# Versorgungseinheit_v1.net
KiCad netlist of a schematic drawn in EAGLE
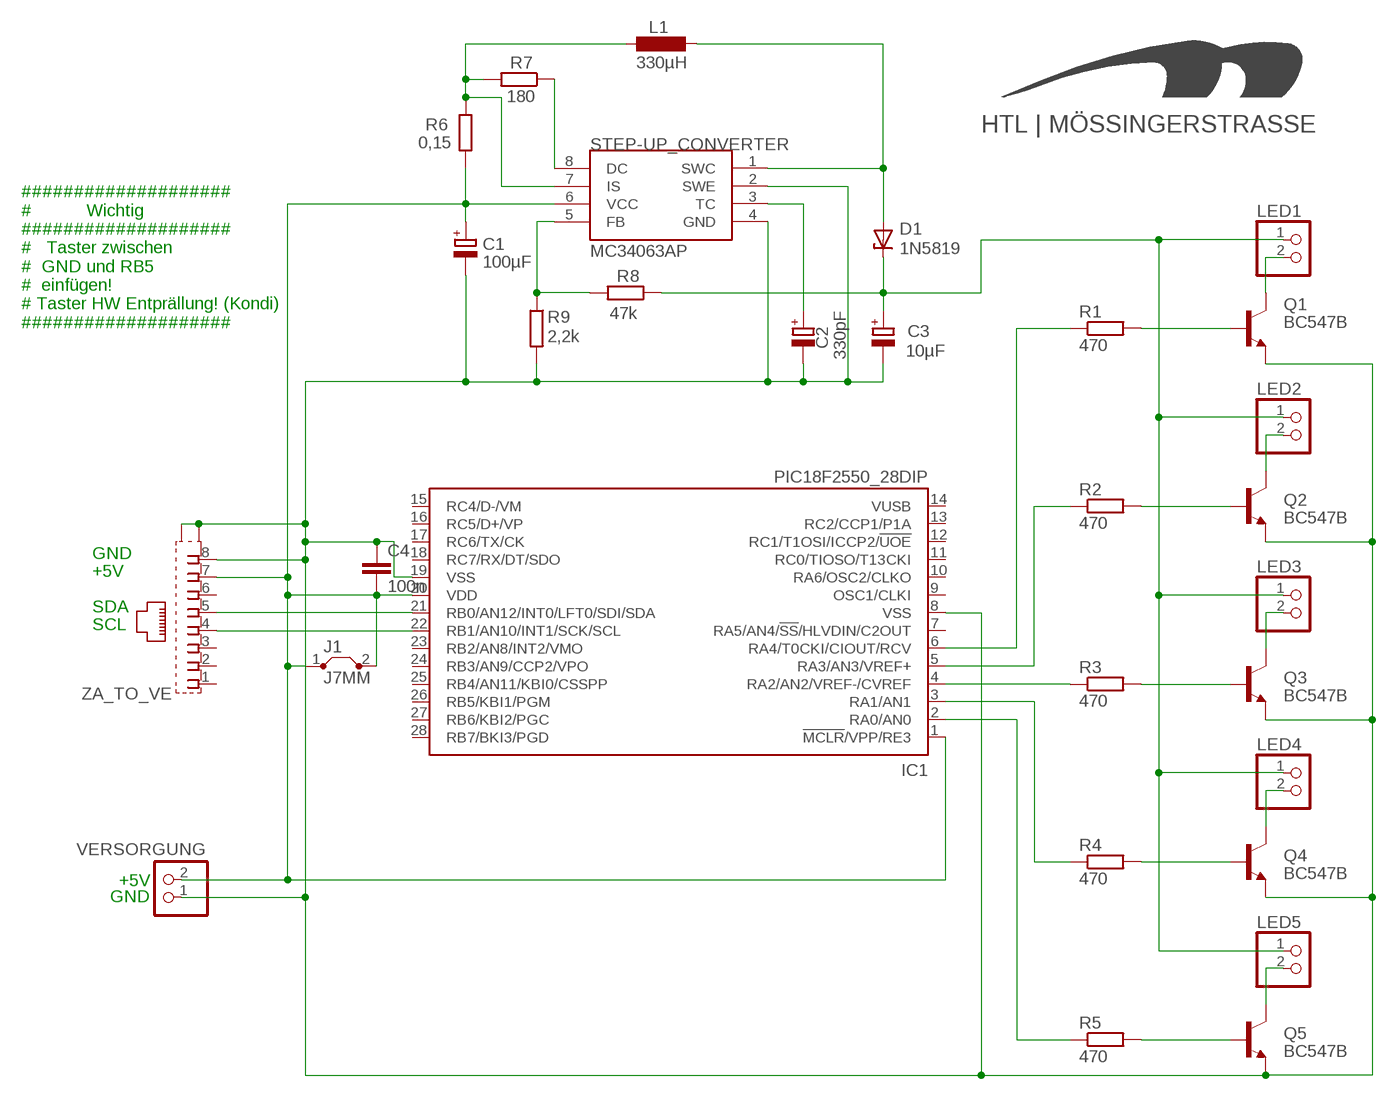
[diagram p0: schematic, sheet 1]

(export (version "E")
  (design (tool "Eeschema 10.0.6"))
  (components
    (comp (ref "C1")
      (value "100µF")
      (footprint "eagle-import:E5-8,5")
      (libsource (lib "eagle-import") (part "CPOL-EUE5-8.5"))
    )
    (comp (ref "C2")
      (value "330pF")
      (footprint "eagle-import:E5-8,5")
      (libsource (lib "eagle-import") (part "CPOL-EUE5-8.5"))
    )
    (comp (ref "C3")
      (value "10µF")
      (footprint "eagle-import:E5-8,5")
      (libsource (lib "eagle-import") (part "CPOL-EUE5-8.5"))
    )
    (comp (ref "C4")
      (value "100n")
      (footprint "eagle-import:C050-025X075")
      (libsource (lib "eagle-import") (part "C-EU050-025X075"))
    )
    (comp (ref "D1")
      (value "1N5819")
      (footprint "eagle-import:DO41Z10")
      (libsource (lib "eagle-import") (part "1N4728"))
    )
    (comp (ref "IC1")
      (value "PIC18F2550_28DIP")
      (footprint "eagle-import:DIL28-3")
      (fields (field (name "MF") "MICROCHIP") (field (name "MPN") "PIC18F2550-I/SP"))
      (libsource (lib "eagle-import") (part "PIC18F2_28DIP550"))
    )
    (comp (ref "J1")
      (value "J7MM")
      (footprint "eagle-import:07")
      (libsource (lib "eagle-import") (part "J7MM"))
    )
    (comp (ref "L1")
      (value "330µH")
      (footprint "eagle-import:0207_10")
      (libsource (lib "eagle-import") (part "L-EU0207/10"))
    )
    (comp (ref "LED1")
      (value "PINHD-1X2")
      (footprint "eagle-import:1X02")
      (libsource (lib "eagle-import") (part "PINHD-1X2"))
    )
    (comp (ref "LED2")
      (value "PINHD-1X2")
      (footprint "eagle-import:1X02")
      (libsource (lib "eagle-import") (part "PINHD-1X2"))
    )
    (comp (ref "LED3")
      (value "PINHD-1X2")
      (footprint "eagle-import:1X02")
      (libsource (lib "eagle-import") (part "PINHD-1X2"))
    )
    (comp (ref "LED4")
      (value "PINHD-1X2")
      (footprint "eagle-import:1X02")
      (libsource (lib "eagle-import") (part "PINHD-1X2"))
    )
    (comp (ref "LED5")
      (value "PINHD-1X2")
      (footprint "eagle-import:1X02")
      (libsource (lib "eagle-import") (part "PINHD-1X2"))
    )
    (comp (ref "Q1")
      (value "BC547B")
      (footprint "eagle-import:TO92")
      (libsource (lib "eagle-import") (part "BC547B"))
    )
    (comp (ref "Q2")
      (value "BC547B")
      (footprint "eagle-import:TO92")
      (libsource (lib "eagle-import") (part "BC547B"))
    )
    (comp (ref "Q3")
      (value "BC547B")
      (footprint "eagle-import:TO92")
      (libsource (lib "eagle-import") (part "BC547B"))
    )
    (comp (ref "Q4")
      (value "BC547B")
      (footprint "eagle-import:TO92")
      (libsource (lib "eagle-import") (part "BC547B"))
    )
    (comp (ref "Q5")
      (value "BC547B")
      (footprint "eagle-import:TO92")
      (libsource (lib "eagle-import") (part "BC547B"))
    )
    (comp (ref "R1")
      (value "470")
      (footprint "eagle-import:0207_10")
      (libsource (lib "eagle-import") (part "R-EU_0207/10"))
    )
    (comp (ref "R2")
      (value "470")
      (footprint "eagle-import:0207_10")
      (libsource (lib "eagle-import") (part "R-EU_0207/10"))
    )
    (comp (ref "R3")
      (value "470")
      (footprint "eagle-import:0207_10")
      (libsource (lib "eagle-import") (part "R-EU_0207/10"))
    )
    (comp (ref "R4")
      (value "470")
      (footprint "eagle-import:0207_10")
      (libsource (lib "eagle-import") (part "R-EU_0207/10"))
    )
    (comp (ref "R5")
      (value "470")
      (footprint "eagle-import:0207_10")
      (libsource (lib "eagle-import") (part "R-EU_0207/10"))
    )
    (comp (ref "R6")
      (value "0,15")
      (footprint "eagle-import:R1206")
      (libsource (lib "eagle-import") (part "R-EU_R1206"))
    )
    (comp (ref "R7")
      (value "180")
      (footprint "eagle-import:0207_10")
      (libsource (lib "eagle-import") (part "R-EU_0207/10"))
    )
    (comp (ref "R8")
      (value "47k")
      (footprint "eagle-import:0207_10")
      (libsource (lib "eagle-import") (part "R-EU_0207/10"))
    )
    (comp (ref "R9")
      (value "2,2k")
      (footprint "eagle-import:0207_10")
      (libsource (lib "eagle-import") (part "R-EU_0207/10"))
    )
    (comp (ref "STEP-UP_CONVERTER")
      (value "MC34063AP")
      (footprint "eagle-import:DIL08")
      (libsource (lib "eagle-import") (part "MC34063AP"))
    )
    (comp (ref "U$2")
      (value "HTL_LOGOBOT_15MM")
      (footprint "eagle-import:LOGOBOT_15")
      (libsource (lib "eagle-import") (part "HTL_LOGOBOT_15MM"))
    )
    (comp (ref "VERSORGUNG")
      (value "PINHD-1X2")
      (footprint "eagle-import:1X02")
      (libsource (lib "eagle-import") (part "PINHD-1X2"))
    )
    (comp (ref "ZA_TO_VE")
      (value "555141-1")
      (footprint "eagle-import:555153-1")
      (libsource (lib "eagle-import") (part "555141-1"))
    )
  )
  (nets
    (net (code "1") (name "Net-(C3-Pad+)") (class "Default")
      (node (ref "C3") (pin "+") (pinfunction "+_+") (pintype "passive"))
      (node (ref "D1") (pin "C") (pinfunction "C_C") (pintype "passive"))
      (node (ref "LED1") (pin "1") (pinfunction "1_1") (pintype "passive"))
      (node (ref "LED2") (pin "1") (pinfunction "1_1") (pintype "passive"))
      (node (ref "LED3") (pin "1") (pinfunction "1_1") (pintype "passive"))
      (node (ref "LED4") (pin "1") (pinfunction "1_1") (pintype "passive"))
      (node (ref "LED5") (pin "1") (pinfunction "1_1") (pintype "passive"))
      (node (ref "R8") (pin "1") (pinfunction "1_1") (pintype "passive"))
    )
    (net (code "2") (name "Net-(IC1-RA0{slash}AN0)") (class "Default")
      (node (ref "IC1") (pin "2") (pinfunction "RA0/AN0_2") (pintype "bidirectional"))
      (node (ref "R5") (pin "1") (pinfunction "1_1") (pintype "passive"))
    )
    (net (code "3") (name "Net-(IC1-RA1{slash}AN1)") (class "Default")
      (node (ref "IC1") (pin "3") (pinfunction "RA1/AN1_3") (pintype "bidirectional"))
      (node (ref "R4") (pin "1") (pinfunction "1_1") (pintype "passive"))
    )
    (net (code "4") (name "Net-(IC1-RA2{slash}AN2{slash}VREF-{slash}CVREF)") (class "Default")
      (node (ref "IC1") (pin "4") (pinfunction "RA2/AN2/VREF-/CVREF_4") (pintype "bidirectional"))
      (node (ref "R3") (pin "1") (pinfunction "1_1") (pintype "passive"))
    )
    (net (code "5") (name "Net-(IC1-RA3{slash}AN3{slash}VREF+)") (class "Default")
      (node (ref "IC1") (pin "5") (pinfunction "RA3/AN3/VREF+_5") (pintype "bidirectional"))
      (node (ref "R2") (pin "1") (pinfunction "1_1") (pintype "passive"))
    )
    (net (code "6") (name "Net-(IC1-RA4{slash}T0CKI{slash}CIOUT{slash}RCV)") (class "Default")
      (node (ref "IC1") (pin "6") (pinfunction "RA4/T0CKI/CIOUT/RCV_6") (pintype "bidirectional"))
      (node (ref "R1") (pin "1") (pinfunction "1_1") (pintype "passive"))
    )
    (net (code "7") (name "Net-(IC1-RB0{slash}AN12{slash}INT0{slash}LFT0{slash}SDI{slash}SDA)") (class "Default")
      (node (ref "IC1") (pin "21") (pinfunction "RB0/AN12/INT0/LFT0/SDI/SDA_21") (pintype "bidirectional"))
      (node (ref "ZA_TO_VE") (pin "5") (pinfunction "5_5") (pintype "passive"))
    )
    (net (code "8") (name "Net-(IC1-RB1{slash}AN10{slash}INT1{slash}SCK{slash}SCL)") (class "Default")
      (node (ref "IC1") (pin "22") (pinfunction "RB1/AN10/INT1/SCK/SCL_22") (pintype "bidirectional"))
      (node (ref "ZA_TO_VE") (pin "4") (pinfunction "4_4") (pintype "passive"))
    )
    (net (code "9") (name "Net-(IC1-VDD)") (class "Default")
      (node (ref "C1") (pin "+") (pinfunction "+_+") (pintype "passive"))
      (node (ref "C4") (pin "2") (pinfunction "2_2") (pintype "passive"))
      (node (ref "IC1") (pin "1") (pinfunction "~{MCLR}/VPP/RE3_1") (pintype "input"))
      (node (ref "IC1") (pin "20") (pinfunction "VDD_20") (pintype "power_in"))
      (node (ref "J1") (pin "1") (pinfunction "1_1") (pintype "passive"))
      (node (ref "J1") (pin "2") (pinfunction "2_2") (pintype "passive"))
      (node (ref "R6") (pin "1") (pinfunction "1_1") (pintype "passive"))
      (node (ref "STEP-UP_CONVERTER") (pin "6") (pinfunction "VCC_6") (pintype "passive"))
      (node (ref "VERSORGUNG") (pin "2") (pinfunction "2_2") (pintype "passive"))
      (node (ref "ZA_TO_VE") (pin "7") (pinfunction "7_7") (pintype "passive"))
    )
    (net (code "10") (name "Net-(Q1-B)") (class "Default")
      (node (ref "Q1") (pin "2") (pinfunction "B_2") (pintype "passive"))
      (node (ref "R1") (pin "2") (pinfunction "2_2") (pintype "passive"))
    )
    (net (code "11") (name "Net-(Q1-C)") (class "Default")
      (node (ref "LED1") (pin "2") (pinfunction "2_2") (pintype "passive"))
      (node (ref "Q1") (pin "3") (pinfunction "C_3") (pintype "passive"))
    )
    (net (code "12") (name "Net-(Q1-E)") (class "Default")
      (node (ref "C1") (pin "-") (pinfunction "-_-") (pintype "passive"))
      (node (ref "C2") (pin "-") (pinfunction "-_-") (pintype "passive"))
      (node (ref "C3") (pin "-") (pinfunction "-_-") (pintype "passive"))
      (node (ref "C4") (pin "1") (pinfunction "1_1") (pintype "passive"))
      (node (ref "IC1") (pin "19") (pinfunction "VSS_19") (pintype "power_in"))
      (node (ref "IC1") (pin "8") (pinfunction "VSS_8") (pintype "power_in"))
      (node (ref "Q1") (pin "1") (pinfunction "E_1") (pintype "passive"))
      (node (ref "Q2") (pin "1") (pinfunction "E_1") (pintype "passive"))
      (node (ref "Q3") (pin "1") (pinfunction "E_1") (pintype "passive"))
      (node (ref "Q4") (pin "1") (pinfunction "E_1") (pintype "passive"))
      (node (ref "Q5") (pin "1") (pinfunction "E_1") (pintype "passive"))
      (node (ref "R9") (pin "2") (pinfunction "2_2") (pintype "passive"))
      (node (ref "STEP-UP_CONVERTER") (pin "2") (pinfunction "SWE_2") (pintype "passive"))
      (node (ref "STEP-UP_CONVERTER") (pin "4") (pinfunction "GND_4") (pintype "passive"))
      (node (ref "VERSORGUNG") (pin "1") (pinfunction "1_1") (pintype "passive"))
      (node (ref "ZA_TO_VE") (pin "8") (pinfunction "8_8") (pintype "passive"))
      (node (ref "ZA_TO_VE") (pin "G1") (pinfunction "S1_G1") (pintype "passive"))
      (node (ref "ZA_TO_VE") (pin "G2") (pinfunction "S2_G2") (pintype "passive"))
    )
    (net (code "13") (name "Net-(Q2-B)") (class "Default")
      (node (ref "Q2") (pin "2") (pinfunction "B_2") (pintype "passive"))
      (node (ref "R2") (pin "2") (pinfunction "2_2") (pintype "passive"))
    )
    (net (code "14") (name "Net-(Q2-C)") (class "Default")
      (node (ref "LED2") (pin "2") (pinfunction "2_2") (pintype "passive"))
      (node (ref "Q2") (pin "3") (pinfunction "C_3") (pintype "passive"))
    )
    (net (code "15") (name "Net-(Q3-B)") (class "Default")
      (node (ref "Q3") (pin "2") (pinfunction "B_2") (pintype "passive"))
      (node (ref "R3") (pin "2") (pinfunction "2_2") (pintype "passive"))
    )
    (net (code "16") (name "Net-(Q3-C)") (class "Default")
      (node (ref "LED3") (pin "2") (pinfunction "2_2") (pintype "passive"))
      (node (ref "Q3") (pin "3") (pinfunction "C_3") (pintype "passive"))
    )
    (net (code "17") (name "Net-(Q4-B)") (class "Default")
      (node (ref "Q4") (pin "2") (pinfunction "B_2") (pintype "passive"))
      (node (ref "R4") (pin "2") (pinfunction "2_2") (pintype "passive"))
    )
    (net (code "18") (name "Net-(Q4-C)") (class "Default")
      (node (ref "LED4") (pin "2") (pinfunction "2_2") (pintype "passive"))
      (node (ref "Q4") (pin "3") (pinfunction "C_3") (pintype "passive"))
    )
    (net (code "19") (name "Net-(Q5-B)") (class "Default")
      (node (ref "Q5") (pin "2") (pinfunction "B_2") (pintype "passive"))
      (node (ref "R5") (pin "2") (pinfunction "2_2") (pintype "passive"))
    )
    (net (code "20") (name "Net-(Q5-C)") (class "Default")
      (node (ref "LED5") (pin "2") (pinfunction "2_2") (pintype "passive"))
      (node (ref "Q5") (pin "3") (pinfunction "C_3") (pintype "passive"))
    )
    (net (code "21") (name "Net-(STEP-UP_CONVERTER-DC)") (class "Default")
      (node (ref "R7") (pin "1") (pinfunction "1_1") (pintype "passive"))
      (node (ref "STEP-UP_CONVERTER") (pin "8") (pinfunction "DC_8") (pintype "passive"))
    )
    (net (code "22") (name "Net-(STEP-UP_CONVERTER-FB)") (class "Default")
      (node (ref "R8") (pin "2") (pinfunction "2_2") (pintype "passive"))
      (node (ref "R9") (pin "1") (pinfunction "1_1") (pintype "passive"))
      (node (ref "STEP-UP_CONVERTER") (pin "5") (pinfunction "FB_5") (pintype "passive"))
    )
    (net (code "23") (name "Net-(STEP-UP_CONVERTER-IS)") (class "Default")
      (node (ref "L1") (pin "2") (pinfunction "2_2") (pintype "passive"))
      (node (ref "R6") (pin "2") (pinfunction "2_2") (pintype "passive"))
      (node (ref "R7") (pin "2") (pinfunction "2_2") (pintype "passive"))
      (node (ref "STEP-UP_CONVERTER") (pin "7") (pinfunction "IS_7") (pintype "passive"))
    )
    (net (code "24") (name "Net-(STEP-UP_CONVERTER-SWC)") (class "Default")
      (node (ref "D1") (pin "A") (pinfunction "A_A") (pintype "passive"))
      (node (ref "L1") (pin "1") (pinfunction "1_1") (pintype "passive"))
      (node (ref "STEP-UP_CONVERTER") (pin "1") (pinfunction "SWC_1") (pintype "passive"))
    )
    (net (code "25") (name "Net-(STEP-UP_CONVERTER-TC)") (class "Default")
      (node (ref "C2") (pin "+") (pinfunction "+_+") (pintype "passive"))
      (node (ref "STEP-UP_CONVERTER") (pin "3") (pinfunction "TC_3") (pintype "passive"))
    )
    (net (code "26") (name "unconnected-(IC1-OSC1{slash}CLKI-Pad9)") (class "Default")
      (node (ref "IC1") (pin "9") (pinfunction "OSC1/CLKI_9") (pintype "input"))
    )
    (net (code "27") (name "unconnected-(IC1-RA5{slash}AN4{slash}~{SS}{slash}HLVDIN{slash}C2OUT-Pad7)") (class "Default")
      (node (ref "IC1") (pin "7") (pinfunction "RA5/AN4/~{SS}/HLVDIN/C2OUT_7") (pintype "bidirectional"))
    )
    (net (code "28") (name "unconnected-(IC1-RA6{slash}OSC2{slash}CLKO-Pad10)") (class "Default")
      (node (ref "IC1") (pin "10") (pinfunction "RA6/OSC2/CLKO_10") (pintype "output"))
    )
    (net (code "29") (name "unconnected-(IC1-RB2{slash}AN8{slash}INT2{slash}VMO-Pad23)") (class "Default")
      (node (ref "IC1") (pin "23") (pinfunction "RB2/AN8/INT2/VMO_23") (pintype "bidirectional"))
    )
    (net (code "30") (name "unconnected-(IC1-RB3{slash}AN9{slash}CCP2{slash}VPO-Pad24)") (class "Default")
      (node (ref "IC1") (pin "24") (pinfunction "RB3/AN9/CCP2/VPO_24") (pintype "bidirectional"))
    )
    (net (code "31") (name "unconnected-(IC1-RB4{slash}AN11{slash}KBI0{slash}CSSPP-Pad25)") (class "Default")
      (node (ref "IC1") (pin "25") (pinfunction "RB4/AN11/KBI0/CSSPP_25") (pintype "bidirectional"))
    )
    (net (code "32") (name "unconnected-(IC1-RB5{slash}KBI1{slash}PGM-Pad26)") (class "Default")
      (node (ref "IC1") (pin "26") (pinfunction "RB5/KBI1/PGM_26") (pintype "bidirectional"))
    )
    (net (code "33") (name "unconnected-(IC1-RB6{slash}KBI2{slash}PGC-Pad27)") (class "Default")
      (node (ref "IC1") (pin "27") (pinfunction "RB6/KBI2/PGC_27") (pintype "bidirectional"))
    )
    (net (code "34") (name "unconnected-(IC1-RB7{slash}BKI3{slash}PGD-Pad28)") (class "Default")
      (node (ref "IC1") (pin "28") (pinfunction "RB7/BKI3/PGD_28") (pintype "bidirectional"))
    )
    (net (code "35") (name "unconnected-(IC1-RC0{slash}TIOSO{slash}T13CKI-Pad11)") (class "Default")
      (node (ref "IC1") (pin "11") (pinfunction "RC0/TIOSO/T13CKI_11") (pintype "bidirectional"))
    )
    (net (code "36") (name "unconnected-(IC1-RC1{slash}T1OSI{slash}ICCP2{slash}~{UOE}-Pad12)") (class "Default")
      (node (ref "IC1") (pin "12") (pinfunction "RC1/T1OSI/ICCP2/~{UOE}_12") (pintype "bidirectional"))
    )
    (net (code "37") (name "unconnected-(IC1-RC2{slash}CCP1{slash}P1A-Pad13)") (class "Default")
      (node (ref "IC1") (pin "13") (pinfunction "RC2/CCP1/P1A_13") (pintype "bidirectional"))
    )
    (net (code "38") (name "unconnected-(IC1-RC4{slash}D-{slash}VM-Pad15)") (class "Default")
      (node (ref "IC1") (pin "15") (pinfunction "RC4/D-/VM_15") (pintype "bidirectional"))
    )
    (net (code "39") (name "unconnected-(IC1-RC5{slash}D+{slash}VP-Pad16)") (class "Default")
      (node (ref "IC1") (pin "16") (pinfunction "RC5/D+/VP_16") (pintype "bidirectional"))
    )
    (net (code "40") (name "unconnected-(IC1-RC6{slash}TX{slash}CK-Pad17)") (class "Default")
      (node (ref "IC1") (pin "17") (pinfunction "RC6/TX/CK_17") (pintype "bidirectional"))
    )
    (net (code "41") (name "unconnected-(IC1-RC7{slash}RX{slash}DT{slash}SDO-Pad18)") (class "Default")
      (node (ref "IC1") (pin "18") (pinfunction "RC7/RX/DT/SDO_18") (pintype "bidirectional"))
    )
    (net (code "42") (name "unconnected-(IC1-VUSB-Pad14)") (class "Default")
      (node (ref "IC1") (pin "14") (pinfunction "VUSB_14") (pintype "bidirectional"))
    )
    (net (code "43") (name "unconnected-(ZA_TO_VE-Pad1)") (class "Default")
      (node (ref "ZA_TO_VE") (pin "1") (pinfunction "1_1") (pintype "passive"))
    )
    (net (code "44") (name "unconnected-(ZA_TO_VE-Pad2)") (class "Default")
      (node (ref "ZA_TO_VE") (pin "2") (pinfunction "2_2") (pintype "passive"))
    )
    (net (code "45") (name "unconnected-(ZA_TO_VE-Pad3)") (class "Default")
      (node (ref "ZA_TO_VE") (pin "3") (pinfunction "3_3") (pintype "passive"))
    )
    (net (code "46") (name "unconnected-(ZA_TO_VE-Pad6)") (class "Default")
      (node (ref "ZA_TO_VE") (pin "6") (pinfunction "6_6") (pintype "passive"))
    )
  )
)
